# Relais2-N_Channel_MOSFET-V001.net
KiCad netlist of a schematic drawn in EAGLE
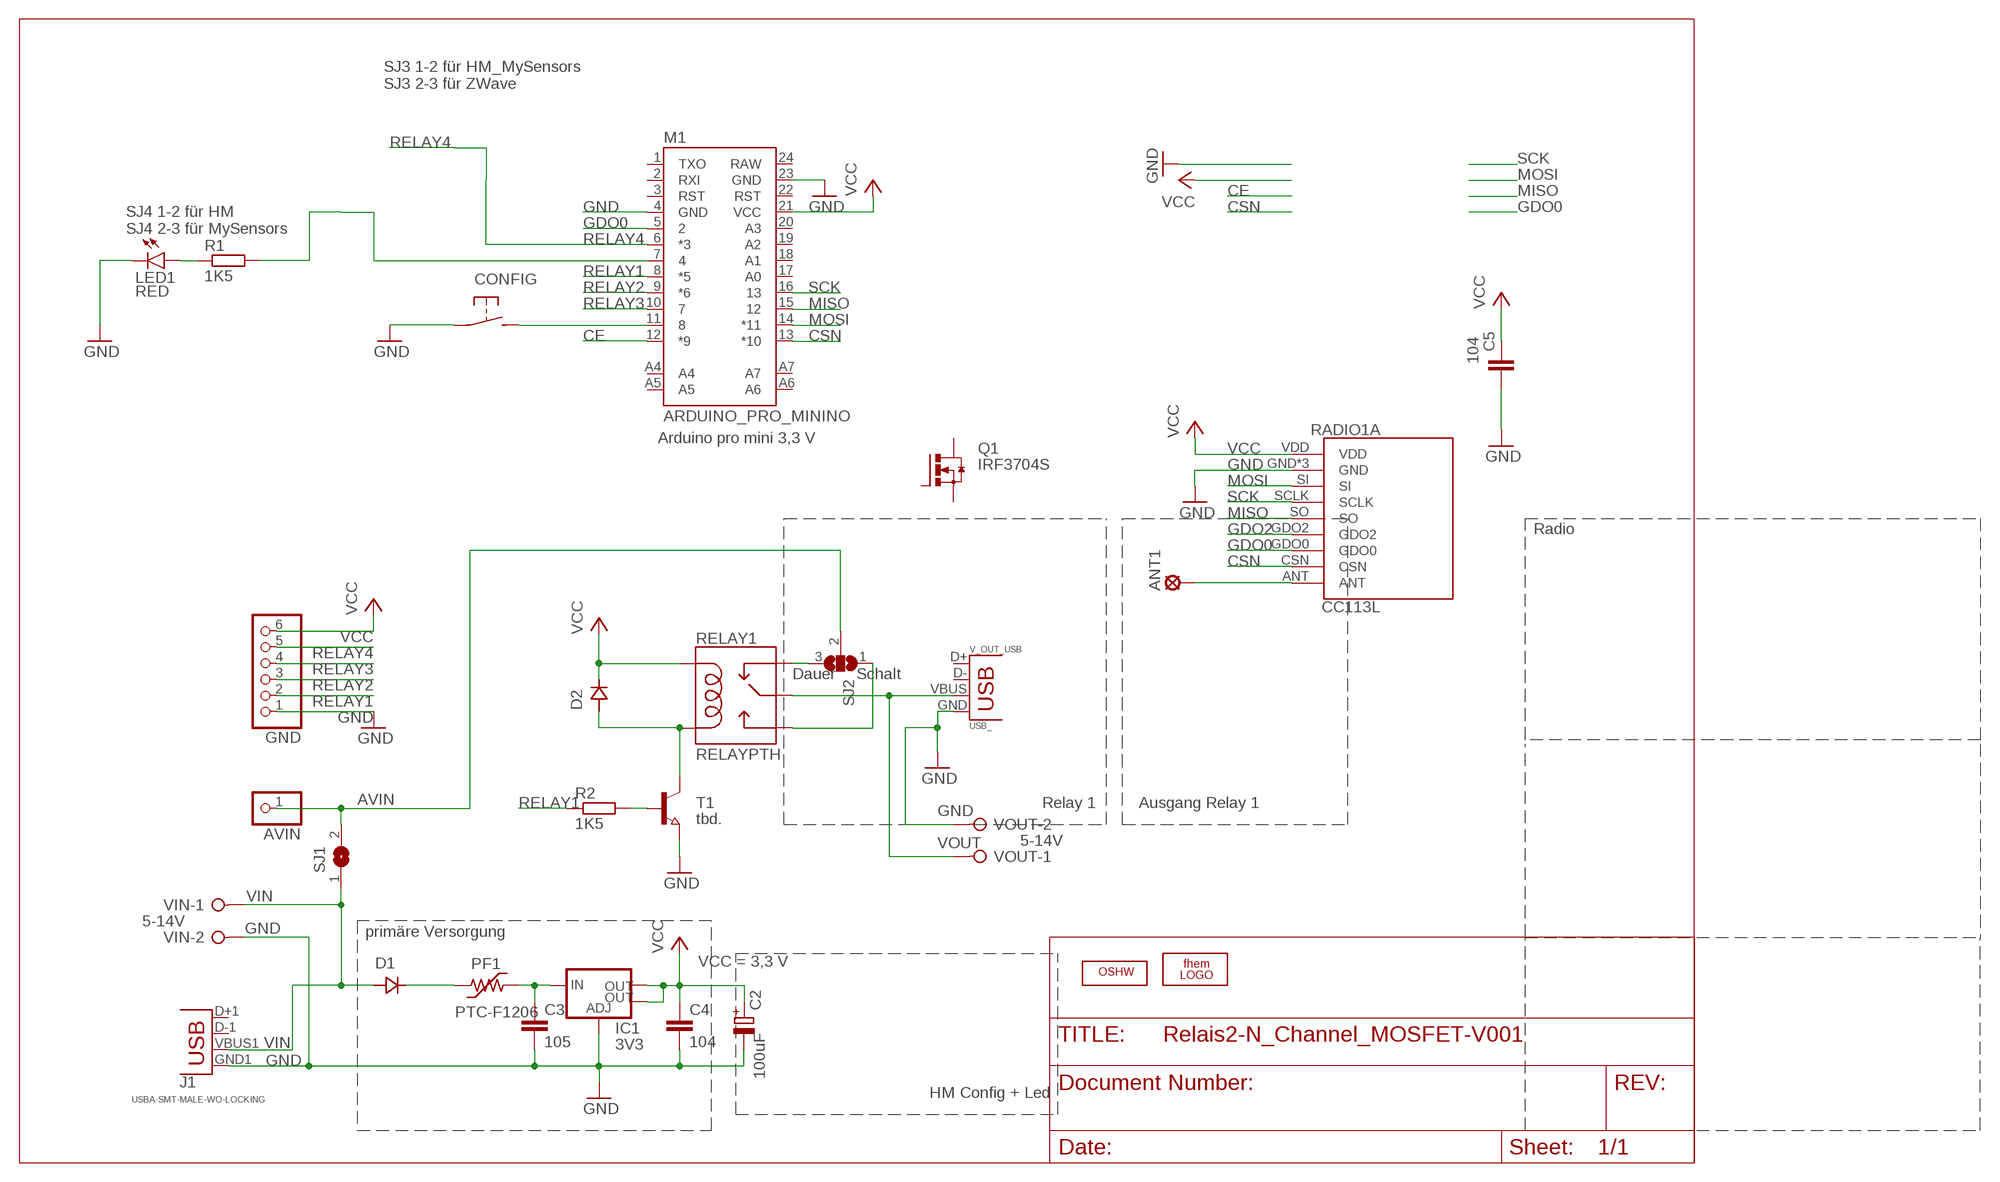
[diagram p0: schematic, sheet 1]

(export (version "E")
  (design (tool "Eeschema 10.0.6"))
  (components
    (comp (ref "ANT1")
      (value "LSP10")
      (footprint "eagle-import:LSP10")
      (libsource (lib "eagle-import") (part "LSP10"))
    )
    (comp (ref "AVIN")
      (value "PINHD-1X1")
      (footprint "eagle-import:1X01")
      (libsource (lib "eagle-import") (part "PINHD-1X1"))
    )
    (comp (ref "C2")
      (value "100uF")
      (footprint "eagle-import:E2,5-6E")
      (libsource (lib "eagle-import") (part "CPOL-EUE2,5-6E"))
    )
    (comp (ref "C3")
      (value "105")
      (footprint "eagle-import:C0805")
      (libsource (lib "eagle-import") (part "C-EUC0805"))
    )
    (comp (ref "C4")
      (value "104")
      (footprint "eagle-import:C0805")
      (libsource (lib "eagle-import") (part "C-EUC0805"))
    )
    (comp (ref "C5")
      (value "104")
      (footprint "eagle-import:C0805")
      (libsource (lib "eagle-import") (part "C-EUC0805"))
    )
    (comp (ref "CONFIG")
      (value "TASTERSMD")
      (footprint "eagle-import:TASTER-SMD")
      (libsource (lib "eagle-import") (part "TASTERSMD"))
    )
    (comp (ref "D1")
      (value "SS14")
      (footprint "eagle-import:DO214")
      (libsource (lib "eagle-import") (part "SS14"))
    )
    (comp (ref "D2")
      (value "SS14")
      (footprint "eagle-import:DO214")
      (libsource (lib "eagle-import") (part "SS14"))
    )
    (comp (ref "GND")
      (value "PINHD-1X6_S")
      (footprint "eagle-import:1X06")
      (libsource (lib "eagle-import") (part "PINHD-1X6_S"))
    )
    (comp (ref "IC1")
      (value "3V3")
      (footprint "eagle-import:SOT223")
      (libsource (lib "eagle-import") (part "V_REG_LM1117SOT223"))
    )
    (comp (ref "J1")
      (value "USBA-SMT-MALE-WO-LOCKING")
      (footprint "eagle-import:USB-A-SMT-MALE-NO_LOCKING")
      (libsource (lib "eagle-import") (part "USBA-SMT-MALE-WO-LOCKING"))
    )
    (comp (ref "LED1")
      (value "RED")
      (footprint "eagle-import:LED-1206")
      (libsource (lib "eagle-import") (part "LED-RED1206"))
    )
    (comp (ref "LOGO2")
      (value "LOGO_OSHWX0070")
      (footprint "eagle-import:OSHW_6X70")
      (libsource (lib "eagle-import") (part "LOGO_OSHWX0070"))
    )
    (comp (ref "M1")
      (value "ARDUINO_PRO_MININO")
      (footprint "eagle-import:ARDUINO_PRO_MINI_O")
      (libsource (lib "eagle-import") (part "ARDUINO_PRO_MININO"))
    )
    (comp (ref "PF1")
      (value "PTC-F1206")
      (footprint "eagle-import:F1206")
      (libsource (lib "eagle-import") (part "PTC-F1206"))
    )
    (comp (ref "Q1")
      (value "IRF3704S")
      (footprint "eagle-import:D2PACK")
      (libsource (lib "eagle-import") (part "IRF3704S"))
    )
    (comp (ref "R1")
      (value "1K5")
      (footprint "eagle-import:R0805_SMALL_GAP")
      (libsource (lib "eagle-import") (part "R0805_SMALL_GAP"))
    )
    (comp (ref "R2")
      (value "1K5")
      (footprint "eagle-import:R0805_SMALL_GAP")
      (libsource (lib "eagle-import") (part "R0805_SMALL_GAP"))
    )
    (comp (ref "RADIO1A")
      (value "CC113L")
      (footprint "eagle-import:CC113L")
      (libsource (lib "eagle-import") (part "CC113L"))
    )
    (comp (ref "RELAY1")
      (value "RELAYPTH")
      (footprint "eagle-import:SRD-05VDC-SL-C")
      (libsource (lib "eagle-import") (part "RELAYPTH"))
    )
    (comp (ref "SJ1") (value "SJ") (footprint "eagle-import:SJ") (libsource (lib "eagle-import") (part "SJ")))
    (comp (ref "SJ2")
      (value "SJ2W")
      (footprint "eagle-import:SJ_2")
      (libsource (lib "eagle-import") (part "SJ2W"))
    )
    (comp (ref "T1")
      (value "tbd.")
      (footprint "eagle-import:SOT89")
      (libsource (lib "eagle-import") (part "NPN-TRANSISTOR_SOT89"))
    )
    (comp (ref "U$2")
      (value "LOGO_FHEMSTOP")
      (footprint "eagle-import:LOGO_FHEM_3X3_STOP")
      (libsource (lib "eagle-import") (part "LOGO_FHEMSTOP"))
    )
    (comp (ref "VIN")
      (value "W237-02P")
      (footprint "eagle-import:W237-132")
      (libsource (lib "eagle-import") (part "W237-02P"))
    )
    (comp (ref "VOUT")
      (value "W237-02P")
      (footprint "eagle-import:W237-132")
      (libsource (lib "eagle-import") (part "W237-02P"))
    )
    (comp (ref "V_OUT_USB")
      (value "USB_")
      (footprint "eagle-import:USB-A-S-SILK-FEMALE")
      (libsource (lib "eagle-import") (part "USB_"))
    )
  )
  (nets
    (net (code "1") (name "/AVIN") (class "Default")
      (node (ref "AVIN") (pin "1") (pinfunction "1_1") (pintype "passive"))
      (node (ref "SJ1") (pin "2") (pinfunction "2_2") (pintype "passive"))
      (node (ref "SJ2") (pin "2") (pinfunction "2_2") (pintype "passive"))
    )
    (net (code "2") (name "/CE") (class "Default")
      (node (ref "M1") (pin "12") (pinfunction "*9_12") (pintype "bidirectional"))
    )
    (net (code "3") (name "/CSN") (class "Default")
      (node (ref "M1") (pin "13") (pinfunction "*10_13") (pintype "bidirectional"))
      (node (ref "RADIO1A") (pin "CSN") (pinfunction "CSN_CSN") (pintype "bidirectional"))
    )
    (net (code "4") (name "/GDO0") (class "Default")
      (node (ref "M1") (pin "5") (pinfunction "2_5") (pintype "bidirectional"))
      (node (ref "RADIO1A") (pin "GDO0") (pinfunction "GDO0_GDO0") (pintype "bidirectional"))
    )
    (net (code "5") (name "/GDO2") (class "Default")
      (node (ref "RADIO1A") (pin "GDO2") (pinfunction "GDO2_GDO2") (pintype "bidirectional"))
    )
    (net (code "6") (name "/MISO") (class "Default")
      (node (ref "M1") (pin "15") (pinfunction "12_15") (pintype "bidirectional"))
      (node (ref "RADIO1A") (pin "SO") (pinfunction "SO_SO") (pintype "bidirectional"))
    )
    (net (code "7") (name "/MOSI") (class "Default")
      (node (ref "M1") (pin "14") (pinfunction "*11_14") (pintype "bidirectional"))
      (node (ref "RADIO1A") (pin "SI") (pinfunction "SI_SI") (pintype "bidirectional"))
    )
    (net (code "8") (name "/RELAY1") (class "Default")
      (node (ref "GND") (pin "2") (pinfunction "2_2") (pintype "passive"))
      (node (ref "M1") (pin "8") (pinfunction "*5_8") (pintype "bidirectional"))
      (node (ref "R2") (pin "1") (pinfunction "1_1") (pintype "passive"))
    )
    (net (code "9") (name "/RELAY2") (class "Default")
      (node (ref "GND") (pin "3") (pinfunction "3_3") (pintype "passive"))
      (node (ref "M1") (pin "9") (pinfunction "*6_9") (pintype "bidirectional"))
    )
    (net (code "10") (name "/RELAY3") (class "Default")
      (node (ref "GND") (pin "4") (pinfunction "4_4") (pintype "passive"))
      (node (ref "M1") (pin "10") (pinfunction "7_10") (pintype "bidirectional"))
    )
    (net (code "11") (name "/RELAY4") (class "Default")
      (node (ref "GND") (pin "5") (pinfunction "5_5") (pintype "passive"))
      (node (ref "M1") (pin "6") (pinfunction "*3_6") (pintype "bidirectional"))
    )
    (net (code "12") (name "/SCK") (class "Default")
      (node (ref "M1") (pin "16") (pinfunction "13_16") (pintype "bidirectional"))
      (node (ref "RADIO1A") (pin "SCLK") (pinfunction "SCLK_SCLK") (pintype "bidirectional"))
    )
    (net (code "13") (name "/VIN") (class "Default")
      (node (ref "D1") (pin "ANODE") (pinfunction "ANODE_ANODE") (pintype "bidirectional"))
      (node (ref "J1") (pin "VBUS1") (pinfunction "VBUS_VBUS1") (pintype "bidirectional"))
      (node (ref "SJ1") (pin "1") (pinfunction "1_1") (pintype "passive"))
      (node (ref "VIN") (pin "1") (pinfunction "KL_1") (pintype "passive"))
    )
    (net (code "14") (name "/VOUT") (class "Default")
      (node (ref "RELAY1") (pin "SWCOMMON") (pinfunction "SWCOMMON_SWCOMMON") (pintype "bidirectional"))
      (node (ref "VOUT") (pin "1") (pinfunction "KL_1") (pintype "passive"))
      (node (ref "V_OUT_USB") (pin "VBUS") (pinfunction "VBUS_VBUS") (pintype "bidirectional"))
    )
    (net (code "15") (name "GND") (class "Default")
      (node (ref "C2") (pin "-") (pinfunction "-_-") (pintype "passive"))
      (node (ref "C3") (pin "2") (pinfunction "2_2") (pintype "passive"))
      (node (ref "C4") (pin "2") (pinfunction "2_2") (pintype "passive"))
      (node (ref "C5") (pin "2") (pinfunction "2_2") (pintype "passive"))
      (node (ref "CONFIG") (pin "1") (pinfunction "P_1") (pintype "passive"))
      (node (ref "GND") (pin "1") (pinfunction "1_1") (pintype "passive"))
      (node (ref "IC1") (pin "1") (pinfunction "ADJ_1") (pintype "power_in"))
      (node (ref "J1") (pin "GND1") (pinfunction "GND_GND1") (pintype "bidirectional"))
      (node (ref "LED1") (pin "C") (pinfunction "C_C") (pintype "passive"))
      (node (ref "M1") (pin "23") (pinfunction "GND_23") (pintype "bidirectional"))
      (node (ref "M1") (pin "4") (pinfunction "GND_4") (pintype "bidirectional"))
      (node (ref "RADIO1A") (pin "GND") (pinfunction "GND_GND") (pintype "power_in"))
      (node (ref "RADIO1A") (pin "GND1") (pinfunction "GND_GND1") (pintype "power_in"))
      (node (ref "RADIO1A") (pin "GND2") (pinfunction "GND_GND2") (pintype "power_in"))
      (node (ref "T1") (pin "3") (pinfunction "E_3") (pintype "passive"))
      (node (ref "VIN") (pin "2") (pinfunction "KL_2") (pintype "passive"))
      (node (ref "VOUT") (pin "2") (pinfunction "KL_2") (pintype "passive"))
      (node (ref "V_OUT_USB") (pin "GND") (pinfunction "GND_GND") (pintype "bidirectional"))
    )
    (net (code "16") (name "Net-(ANT1-MP)") (class "Default")
      (node (ref "ANT1") (pin "1") (pinfunction "MP_1") (pintype "passive"))
      (node (ref "RADIO1A") (pin "ANT") (pinfunction "ANT_ANT") (pintype "bidirectional"))
    )
    (net (code "17") (name "Net-(CONFIG-S)") (class "Default")
      (node (ref "CONFIG") (pin "2") (pinfunction "S_2") (pintype "passive"))
      (node (ref "M1") (pin "11") (pinfunction "8_11") (pintype "bidirectional"))
    )
    (net (code "18") (name "Net-(D1-PadCATHODE)") (class "Default")
      (node (ref "D1") (pin "CATHODE") (pinfunction "CATHODE_CATHODE") (pintype "bidirectional"))
      (node (ref "PF1") (pin "1") (pinfunction "1_1") (pintype "passive"))
    )
    (net (code "19") (name "Net-(IC1-IN)") (class "Default")
      (node (ref "C3") (pin "1") (pinfunction "1_1") (pintype "passive"))
      (node (ref "IC1") (pin "3") (pinfunction "IN_3") (pintype "power_in"))
      (node (ref "PF1") (pin "2") (pinfunction "2_2") (pintype "passive"))
    )
    (net (code "20") (name "Net-(LED1-PadA)") (class "Default")
      (node (ref "LED1") (pin "A") (pinfunction "A_A") (pintype "passive"))
      (node (ref "R1") (pin "1") (pinfunction "1_1") (pintype "passive"))
    )
    (net (code "21") (name "Net-(M1-4)") (class "Default")
      (node (ref "M1") (pin "7") (pinfunction "4_7") (pintype "bidirectional"))
      (node (ref "R1") (pin "2") (pinfunction "2_2") (pintype "passive"))
    )
    (net (code "22") (name "Net-(RELAY1-PadSWOPEN)") (class "Default")
      (node (ref "RELAY1") (pin "SWOPEN") (pinfunction "SWOPEN_SWOPEN") (pintype "bidirectional"))
      (node (ref "SJ2") (pin "1") (pinfunction "1_1") (pintype "passive"))
    )
    (net (code "23") (name "Net-(RELAY1-SWCLOSE)") (class "Default")
      (node (ref "RELAY1") (pin "SWCLOSED") (pinfunction "SWCLOSE_SWCLOSED") (pintype "bidirectional"))
      (node (ref "SJ2") (pin "3") (pinfunction "3_3") (pintype "passive"))
    )
    (net (code "24") (name "Net-(T1-B)") (class "Default")
      (node (ref "R2") (pin "2") (pinfunction "2_2") (pintype "passive"))
      (node (ref "T1") (pin "1") (pinfunction "B_1") (pintype "passive"))
    )
    (net (code "25") (name "Net-(T1-C)") (class "Default")
      (node (ref "D2") (pin "ANODE") (pinfunction "ANODE_ANODE") (pintype "bidirectional"))
      (node (ref "RELAY1") (pin "COIL0") (pinfunction "COIL0_COIL0") (pintype "bidirectional"))
      (node (ref "T1") (pin "2") (pinfunction "C_2") (pintype "passive"))
    )
    (net (code "26") (name "VCC") (class "Default")
      (node (ref "C2") (pin "+") (pinfunction "+_+") (pintype "passive"))
      (node (ref "C4") (pin "1") (pinfunction "1_1") (pintype "passive"))
      (node (ref "C5") (pin "1") (pinfunction "1_1") (pintype "passive"))
      (node (ref "D2") (pin "CATHODE") (pinfunction "CATHODE_CATHODE") (pintype "bidirectional"))
      (node (ref "GND") (pin "6") (pinfunction "6_6") (pintype "passive"))
      (node (ref "IC1") (pin "2") (pinfunction "OUT_2") (pintype "power_in"))
      (node (ref "IC1") (pin "4") (pinfunction "OUT_4") (pintype "power_in"))
      (node (ref "M1") (pin "21") (pinfunction "VCC_21") (pintype "bidirectional"))
      (node (ref "RADIO1A") (pin "VDD") (pinfunction "VDD_VDD") (pintype "power_in"))
      (node (ref "RELAY1") (pin "COIL1") (pinfunction "COIL1_COIL1") (pintype "bidirectional"))
    )
    (net (code "27") (name "unconnected-(J1-D+-PadD+1)") (class "Default")
      (node (ref "J1") (pin "D+1") (pinfunction "D+_D+1") (pintype "bidirectional"))
    )
    (net (code "28") (name "unconnected-(J1-D--PadD-1)") (class "Default")
      (node (ref "J1") (pin "D-1") (pinfunction "D-_D-1") (pintype "bidirectional"))
    )
    (net (code "29") (name "unconnected-(M1-A0-Pad17)") (class "Default")
      (node (ref "M1") (pin "17") (pinfunction "A0_17") (pintype "bidirectional"))
    )
    (net (code "30") (name "unconnected-(M1-A1-Pad18)") (class "Default")
      (node (ref "M1") (pin "18") (pinfunction "A1_18") (pintype "bidirectional"))
    )
    (net (code "31") (name "unconnected-(M1-A2-Pad19)") (class "Default")
      (node (ref "M1") (pin "19") (pinfunction "A2_19") (pintype "bidirectional"))
    )
    (net (code "32") (name "unconnected-(M1-A3-Pad20)") (class "Default")
      (node (ref "M1") (pin "20") (pinfunction "A3_20") (pintype "bidirectional"))
    )
    (net (code "33") (name "unconnected-(M1-PadA4)") (class "Default")
      (node (ref "M1") (pin "A4") (pinfunction "A4_A4") (pintype "bidirectional"))
    )
    (net (code "34") (name "unconnected-(M1-PadA5)") (class "Default")
      (node (ref "M1") (pin "A5") (pinfunction "A5_A5") (pintype "bidirectional"))
    )
    (net (code "35") (name "unconnected-(M1-PadA6)") (class "Default")
      (node (ref "M1") (pin "A6") (pinfunction "A6_A6") (pintype "bidirectional"))
    )
    (net (code "36") (name "unconnected-(M1-PadA7)") (class "Default")
      (node (ref "M1") (pin "A7") (pinfunction "A7_A7") (pintype "bidirectional"))
    )
    (net (code "37") (name "unconnected-(M1-RAW-Pad24)") (class "Default")
      (node (ref "M1") (pin "24") (pinfunction "RAW_24") (pintype "bidirectional"))
    )
    (net (code "38") (name "unconnected-(M1-RST-Pad3)") (class "Default")
      (node (ref "M1") (pin "3") (pinfunction "RST_3") (pintype "bidirectional"))
    )
    (net (code "39") (name "unconnected-(M1-RST-Pad22)") (class "Default")
      (node (ref "M1") (pin "22") (pinfunction "RST_22") (pintype "bidirectional"))
    )
    (net (code "40") (name "unconnected-(M1-RXI-Pad2)") (class "Default")
      (node (ref "M1") (pin "2") (pinfunction "RXI_2") (pintype "bidirectional"))
    )
    (net (code "41") (name "unconnected-(M1-TXO-Pad1)") (class "Default")
      (node (ref "M1") (pin "1") (pinfunction "TXO_1") (pintype "bidirectional"))
    )
    (net (code "42") (name "unconnected-(Q1-D-Pad2)") (class "Default")
      (node (ref "Q1") (pin "2") (pinfunction "D_2") (pintype "passive"))
    )
    (net (code "43") (name "unconnected-(Q1-G-Pad1)") (class "Default")
      (node (ref "Q1") (pin "1") (pinfunction "G_1") (pintype "passive"))
    )
    (net (code "44") (name "unconnected-(Q1-S-Pad3)") (class "Default")
      (node (ref "Q1") (pin "3") (pinfunction "S_3") (pintype "passive"))
    )
    (net (code "45") (name "unconnected-(V_OUT_USB-PadD+)") (class "Default")
      (node (ref "V_OUT_USB") (pin "D+") (pinfunction "D+_D+") (pintype "bidirectional"))
    )
    (net (code "46") (name "unconnected-(V_OUT_USB-PadD-)") (class "Default")
      (node (ref "V_OUT_USB") (pin "D-") (pinfunction "D-_D-") (pintype "bidirectional"))
    )
  )
)
